# Rib.net
KiCad netlist of a schematic drawn in EAGLE
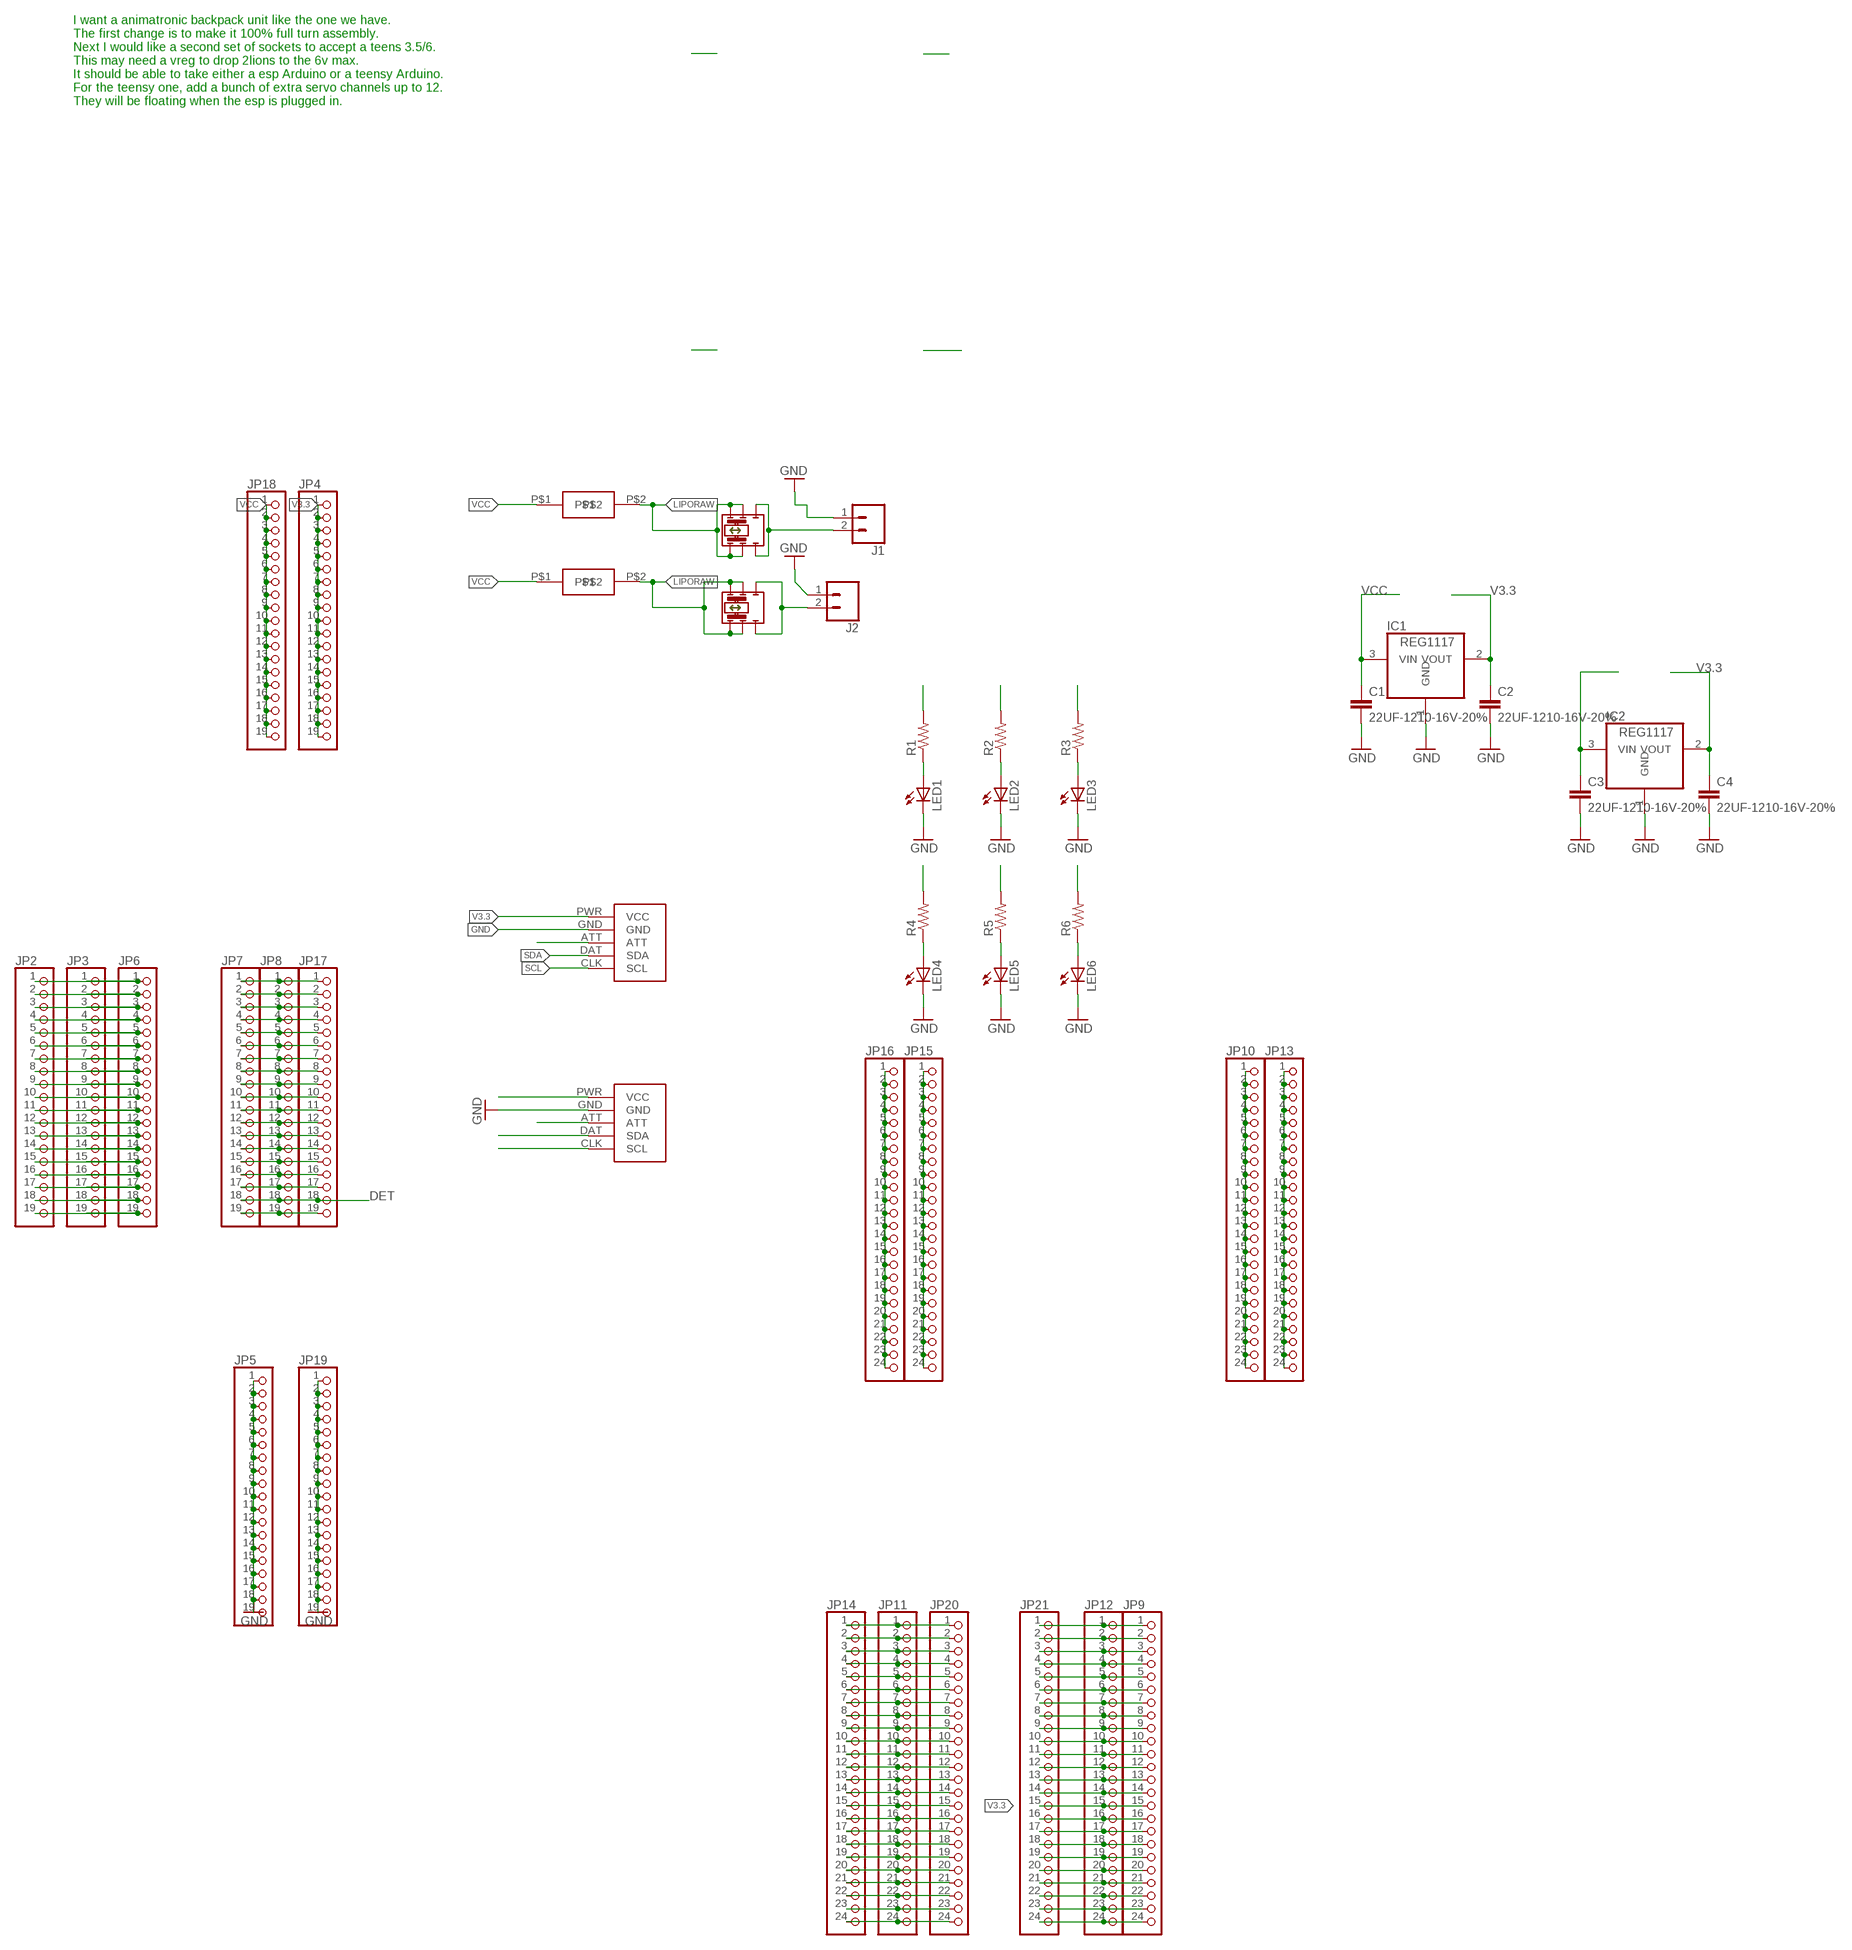
[diagram p0: schematic, sheet 1]

(export (version "E")
  (design (tool "Eeschema 10.0.6"))
  (components
    (comp (ref "C1")
      (value "22UF-1210-16V-20%")
      (footprint "eagle-import:1210")
      (libsource (lib "eagle-import") (part "22UF-1210-16V-20%"))
    )
    (comp (ref "C2")
      (value "22UF-1210-16V-20%")
      (footprint "eagle-import:1210")
      (libsource (lib "eagle-import") (part "22UF-1210-16V-20%"))
    )
    (comp (ref "C3")
      (value "22UF-1210-16V-20%")
      (footprint "eagle-import:1210")
      (libsource (lib "eagle-import") (part "22UF-1210-16V-20%"))
    )
    (comp (ref "C4")
      (value "22UF-1210-16V-20%")
      (footprint "eagle-import:1210")
      (libsource (lib "eagle-import") (part "22UF-1210-16V-20%"))
    )
    (comp (ref "F3")
      (value "3557-2")
      (footprint "eagle-import:3557-2")
      (libsource (lib "eagle-import") (part "3557-2"))
    )
    (comp (ref "F4")
      (value "3557-2")
      (footprint "eagle-import:3557-2")
      (libsource (lib "eagle-import") (part "3557-2"))
    )
    (comp (ref "IC1")
      (value "REG1117")
      (footprint "eagle-import:SOT223")
      (libsource (lib "eagle-import") (part "REG1117"))
    )
    (comp (ref "IC2")
      (value "REG1117")
      (footprint "eagle-import:SOT223")
      (libsource (lib "eagle-import") (part "REG1117"))
    )
    (comp (ref "J1")
      (value "CONN_023.5MM_LOCK")
      (footprint "eagle-import:SCREWTERMINAL-3.5MM-2_LOCK")
      (libsource (lib "eagle-import") (part "CONN_023.5MM_LOCK"))
    )
    (comp (ref "J2")
      (value "CONN_023.5MM_LOCK")
      (footprint "eagle-import:SCREWTERMINAL-3.5MM-2_LOCK")
      (libsource (lib "eagle-import") (part "CONN_023.5MM_LOCK"))
    )
    (comp (ref "JP2")
      (value "PINHD-1X19")
      (footprint "eagle-import:1X19")
      (libsource (lib "eagle-import") (part "PINHD-1X19"))
    )
    (comp (ref "JP3")
      (value "PINHD-1X19")
      (footprint "eagle-import:1X19")
      (libsource (lib "eagle-import") (part "PINHD-1X19"))
    )
    (comp (ref "JP4")
      (value "PINHD-1X19")
      (footprint "eagle-import:1X19")
      (libsource (lib "eagle-import") (part "PINHD-1X19"))
    )
    (comp (ref "JP5")
      (value "PINHD-1X19")
      (footprint "eagle-import:1X19")
      (libsource (lib "eagle-import") (part "PINHD-1X19"))
    )
    (comp (ref "JP6")
      (value "PINHD-1X19")
      (footprint "eagle-import:1X19")
      (libsource (lib "eagle-import") (part "PINHD-1X19"))
    )
    (comp (ref "JP7")
      (value "PINHD-1X19")
      (footprint "eagle-import:1X19")
      (libsource (lib "eagle-import") (part "PINHD-1X19"))
    )
    (comp (ref "JP8")
      (value "PINHD-1X19")
      (footprint "eagle-import:1X19")
      (libsource (lib "eagle-import") (part "PINHD-1X19"))
    )
    (comp (ref "JP9")
      (value "PINHD-1X24")
      (footprint "eagle-import:1X24")
      (libsource (lib "eagle-import") (part "PINHD-1X24"))
    )
    (comp (ref "JP10")
      (value "PINHD-1X24")
      (footprint "eagle-import:1X24")
      (libsource (lib "eagle-import") (part "PINHD-1X24"))
    )
    (comp (ref "JP11")
      (value "PINHD-1X24")
      (footprint "eagle-import:1X24")
      (libsource (lib "eagle-import") (part "PINHD-1X24"))
    )
    (comp (ref "JP12")
      (value "PINHD-1X24")
      (footprint "eagle-import:1X24")
      (libsource (lib "eagle-import") (part "PINHD-1X24"))
    )
    (comp (ref "JP13")
      (value "PINHD-1X24")
      (footprint "eagle-import:1X24")
      (libsource (lib "eagle-import") (part "PINHD-1X24"))
    )
    (comp (ref "JP14")
      (value "PINHD-1X24")
      (footprint "eagle-import:1X24")
      (libsource (lib "eagle-import") (part "PINHD-1X24"))
    )
    (comp (ref "JP15")
      (value "PINHD-1X24")
      (footprint "eagle-import:1X24")
      (libsource (lib "eagle-import") (part "PINHD-1X24"))
    )
    (comp (ref "JP16")
      (value "PINHD-1X24")
      (footprint "eagle-import:1X24")
      (libsource (lib "eagle-import") (part "PINHD-1X24"))
    )
    (comp (ref "JP17")
      (value "PINHD-1X19")
      (footprint "eagle-import:1X19")
      (libsource (lib "eagle-import") (part "PINHD-1X19"))
    )
    (comp (ref "JP18")
      (value "PINHD-1X19")
      (footprint "eagle-import:1X19")
      (libsource (lib "eagle-import") (part "PINHD-1X19"))
    )
    (comp (ref "JP19")
      (value "PINHD-1X19")
      (footprint "eagle-import:1X19")
      (libsource (lib "eagle-import") (part "PINHD-1X19"))
    )
    (comp (ref "JP20")
      (value "PINHD-1X24")
      (footprint "eagle-import:1X24")
      (libsource (lib "eagle-import") (part "PINHD-1X24"))
    )
    (comp (ref "JP21")
      (value "PINHD-1X24")
      (footprint "eagle-import:1X24")
      (libsource (lib "eagle-import") (part "PINHD-1X24"))
    )
    (comp (ref "LED1")
      (value "LED_ESML0603")
      (footprint "eagle-import:LED_SML0603")
      (libsource (lib "eagle-import") (part "LED_ESML0603"))
    )
    (comp (ref "LED2")
      (value "LED_ESML0603")
      (footprint "eagle-import:LED_SML0603")
      (libsource (lib "eagle-import") (part "LED_ESML0603"))
    )
    (comp (ref "LED3")
      (value "LED_ESML0603")
      (footprint "eagle-import:LED_SML0603")
      (libsource (lib "eagle-import") (part "LED_ESML0603"))
    )
    (comp (ref "LED4")
      (value "LED_ESML0603")
      (footprint "eagle-import:LED_SML0603")
      (libsource (lib "eagle-import") (part "LED_ESML0603"))
    )
    (comp (ref "LED5")
      (value "LED_ESML0603")
      (footprint "eagle-import:LED_SML0603")
      (libsource (lib "eagle-import") (part "LED_ESML0603"))
    )
    (comp (ref "LED6")
      (value "LED_ESML0603")
      (footprint "eagle-import:LED_SML0603")
      (libsource (lib "eagle-import") (part "LED_ESML0603"))
    )
    (comp (ref "R1")
      (value "R-US_R0603")
      (footprint "eagle-import:R0603")
      (libsource (lib "eagle-import") (part "R-US_R0603"))
    )
    (comp (ref "R2")
      (value "R-US_R0603")
      (footprint "eagle-import:R0603")
      (libsource (lib "eagle-import") (part "R-US_R0603"))
    )
    (comp (ref "R3")
      (value "R-US_R0603")
      (footprint "eagle-import:R0603")
      (libsource (lib "eagle-import") (part "R-US_R0603"))
    )
    (comp (ref "R4")
      (value "R-US_R0603")
      (footprint "eagle-import:R0603")
      (libsource (lib "eagle-import") (part "R-US_R0603"))
    )
    (comp (ref "R5")
      (value "R-US_R0603")
      (footprint "eagle-import:R0603")
      (libsource (lib "eagle-import") (part "R-US_R0603"))
    )
    (comp (ref "R6")
      (value "R-US_R0603")
      (footprint "eagle-import:R0603")
      (libsource (lib "eagle-import") (part "R-US_R0603"))
    )
    (comp (ref "SW1")
      (value "DPDT")
      (footprint "eagle-import:GF-126-0327")
      (libsource (lib "eagle-import") (part "DPDT"))
    )
    (comp (ref "SW2")
      (value "DPDT")
      (footprint "eagle-import:GF-126-0327")
      (libsource (lib "eagle-import") (part "DPDT"))
    )
    (comp (ref "U$3")
      (value "WIICHUCK")
      (footprint "eagle-import:CHUCK")
      (libsource (lib "eagle-import") (part "WIICHUCK"))
    )
    (comp (ref "U$5")
      (value "WIICHUCK")
      (footprint "eagle-import:CHUCK")
      (libsource (lib "eagle-import") (part "WIICHUCK"))
    )
  )
  (nets
    (net (code "1") (name "/5V") (class "Default")
      (node (ref "JP11") (pin "1") (pinfunction "1_1") (pintype "passive"))
      (node (ref "JP14") (pin "1") (pinfunction "1_1") (pintype "passive"))
      (node (ref "JP2") (pin "1") (pinfunction "1_1") (pintype "passive"))
      (node (ref "JP20") (pin "1") (pinfunction "1_1") (pintype "passive"))
      (node (ref "JP3") (pin "1") (pinfunction "1_1") (pintype "passive"))
      (node (ref "JP6") (pin "1") (pinfunction "1_1") (pintype "passive"))
    )
    (net (code "2") (name "/DET") (class "Default")
      (node (ref "JP12") (pin "24") (pinfunction "24_24") (pintype "passive"))
      (node (ref "JP17") (pin "18") (pinfunction "18_18") (pintype "passive"))
      (node (ref "JP21") (pin "24") (pinfunction "24_24") (pintype "passive"))
      (node (ref "JP7") (pin "18") (pinfunction "18_18") (pintype "passive"))
      (node (ref "JP8") (pin "18") (pinfunction "18_18") (pintype "passive"))
      (node (ref "JP9") (pin "24") (pinfunction "24_24") (pintype "passive"))
      (node (ref "U$3") (pin "ATT") (pinfunction "ATT_ATT") (pintype "bidirectional"))
      (node (ref "U$5") (pin "ATT") (pinfunction "ATT_ATT") (pintype "bidirectional"))
    )
    (net (code "3") (name "/RX0") (class "Default")
      (node (ref "JP12") (pin "12") (pinfunction "12_12") (pintype "passive"))
      (node (ref "JP17") (pin "15") (pinfunction "15_15") (pintype "passive"))
      (node (ref "JP21") (pin "12") (pinfunction "12_12") (pintype "passive"))
      (node (ref "JP7") (pin "15") (pinfunction "15_15") (pintype "passive"))
      (node (ref "JP8") (pin "15") (pinfunction "15_15") (pintype "passive"))
      (node (ref "JP9") (pin "12") (pinfunction "12_12") (pintype "passive"))
    )
    (net (code "4") (name "/TX0") (class "Default")
      (node (ref "JP12") (pin "11") (pinfunction "11_11") (pintype "passive"))
      (node (ref "JP17") (pin "16") (pinfunction "16_16") (pintype "passive"))
      (node (ref "JP21") (pin "11") (pinfunction "11_11") (pintype "passive"))
      (node (ref "JP7") (pin "16") (pinfunction "16_16") (pintype "passive"))
      (node (ref "JP8") (pin "16") (pinfunction "16_16") (pintype "passive"))
      (node (ref "JP9") (pin "11") (pinfunction "11_11") (pintype "passive"))
    )
    (net (code "5") (name "GND") (class "Default")
      (node (ref "C1") (pin "2") (pinfunction "2_2") (pintype "passive"))
      (node (ref "C2") (pin "2") (pinfunction "2_2") (pintype "passive"))
      (node (ref "C3") (pin "2") (pinfunction "2_2") (pintype "passive"))
      (node (ref "C4") (pin "2") (pinfunction "2_2") (pintype "passive"))
      (node (ref "IC1") (pin "1") (pinfunction "GND_1") (pintype "power_in"))
      (node (ref "IC2") (pin "1") (pinfunction "GND_1") (pintype "power_in"))
      (node (ref "J1") (pin "1") (pinfunction "1_1") (pintype "passive"))
      (node (ref "J2") (pin "1") (pinfunction "1_1") (pintype "passive"))
      (node (ref "JP11") (pin "15") (pinfunction "15_15") (pintype "passive"))
      (node (ref "JP11") (pin "2") (pinfunction "2_2") (pintype "passive"))
      (node (ref "JP12") (pin "1") (pinfunction "1_1") (pintype "passive"))
      (node (ref "JP13") (pin "1") (pinfunction "1_1") (pintype "passive"))
      (node (ref "JP13") (pin "10") (pinfunction "10_10") (pintype "passive"))
      (node (ref "JP13") (pin "11") (pinfunction "11_11") (pintype "passive"))
      (node (ref "JP13") (pin "12") (pinfunction "12_12") (pintype "passive"))
      (node (ref "JP13") (pin "13") (pinfunction "13_13") (pintype "passive"))
      (node (ref "JP13") (pin "14") (pinfunction "14_14") (pintype "passive"))
      (node (ref "JP13") (pin "15") (pinfunction "15_15") (pintype "passive"))
      (node (ref "JP13") (pin "16") (pinfunction "16_16") (pintype "passive"))
      (node (ref "JP13") (pin "17") (pinfunction "17_17") (pintype "passive"))
      (node (ref "JP13") (pin "18") (pinfunction "18_18") (pintype "passive"))
      (node (ref "JP13") (pin "19") (pinfunction "19_19") (pintype "passive"))
      (node (ref "JP13") (pin "2") (pinfunction "2_2") (pintype "passive"))
      (node (ref "JP13") (pin "20") (pinfunction "20_20") (pintype "passive"))
      (node (ref "JP13") (pin "21") (pinfunction "21_21") (pintype "passive"))
      (node (ref "JP13") (pin "22") (pinfunction "22_22") (pintype "passive"))
      (node (ref "JP13") (pin "23") (pinfunction "23_23") (pintype "passive"))
      (node (ref "JP13") (pin "24") (pinfunction "24_24") (pintype "passive"))
      (node (ref "JP13") (pin "3") (pinfunction "3_3") (pintype "passive"))
      (node (ref "JP13") (pin "4") (pinfunction "4_4") (pintype "passive"))
      (node (ref "JP13") (pin "5") (pinfunction "5_5") (pintype "passive"))
      (node (ref "JP13") (pin "6") (pinfunction "6_6") (pintype "passive"))
      (node (ref "JP13") (pin "7") (pinfunction "7_7") (pintype "passive"))
      (node (ref "JP13") (pin "8") (pinfunction "8_8") (pintype "passive"))
      (node (ref "JP13") (pin "9") (pinfunction "9_9") (pintype "passive"))
      (node (ref "JP14") (pin "15") (pinfunction "15_15") (pintype "passive"))
      (node (ref "JP14") (pin "2") (pinfunction "2_2") (pintype "passive"))
      (node (ref "JP16") (pin "1") (pinfunction "1_1") (pintype "passive"))
      (node (ref "JP16") (pin "10") (pinfunction "10_10") (pintype "passive"))
      (node (ref "JP16") (pin "11") (pinfunction "11_11") (pintype "passive"))
      (node (ref "JP16") (pin "12") (pinfunction "12_12") (pintype "passive"))
      (node (ref "JP16") (pin "13") (pinfunction "13_13") (pintype "passive"))
      (node (ref "JP16") (pin "14") (pinfunction "14_14") (pintype "passive"))
      (node (ref "JP16") (pin "15") (pinfunction "15_15") (pintype "passive"))
      (node (ref "JP16") (pin "16") (pinfunction "16_16") (pintype "passive"))
      (node (ref "JP16") (pin "17") (pinfunction "17_17") (pintype "passive"))
      (node (ref "JP16") (pin "18") (pinfunction "18_18") (pintype "passive"))
      (node (ref "JP16") (pin "19") (pinfunction "19_19") (pintype "passive"))
      (node (ref "JP16") (pin "2") (pinfunction "2_2") (pintype "passive"))
      (node (ref "JP16") (pin "20") (pinfunction "20_20") (pintype "passive"))
      (node (ref "JP16") (pin "21") (pinfunction "21_21") (pintype "passive"))
      (node (ref "JP16") (pin "22") (pinfunction "22_22") (pintype "passive"))
      (node (ref "JP16") (pin "23") (pinfunction "23_23") (pintype "passive"))
      (node (ref "JP16") (pin "24") (pinfunction "24_24") (pintype "passive"))
      (node (ref "JP16") (pin "3") (pinfunction "3_3") (pintype "passive"))
      (node (ref "JP16") (pin "4") (pinfunction "4_4") (pintype "passive"))
      (node (ref "JP16") (pin "5") (pinfunction "5_5") (pintype "passive"))
      (node (ref "JP16") (pin "6") (pinfunction "6_6") (pintype "passive"))
      (node (ref "JP16") (pin "7") (pinfunction "7_7") (pintype "passive"))
      (node (ref "JP16") (pin "8") (pinfunction "8_8") (pintype "passive"))
      (node (ref "JP16") (pin "9") (pinfunction "9_9") (pintype "passive"))
      (node (ref "JP17") (pin "13") (pinfunction "13_13") (pintype "passive"))
      (node (ref "JP17") (pin "19") (pinfunction "19_19") (pintype "passive"))
      (node (ref "JP19") (pin "1") (pinfunction "1_1") (pintype "passive"))
      (node (ref "JP19") (pin "10") (pinfunction "10_10") (pintype "passive"))
      (node (ref "JP19") (pin "11") (pinfunction "11_11") (pintype "passive"))
      (node (ref "JP19") (pin "12") (pinfunction "12_12") (pintype "passive"))
      (node (ref "JP19") (pin "13") (pinfunction "13_13") (pintype "passive"))
      (node (ref "JP19") (pin "14") (pinfunction "14_14") (pintype "passive"))
      (node (ref "JP19") (pin "15") (pinfunction "15_15") (pintype "passive"))
      (node (ref "JP19") (pin "16") (pinfunction "16_16") (pintype "passive"))
      (node (ref "JP19") (pin "17") (pinfunction "17_17") (pintype "passive"))
      (node (ref "JP19") (pin "18") (pinfunction "18_18") (pintype "passive"))
      (node (ref "JP19") (pin "19") (pinfunction "19_19") (pintype "passive"))
      (node (ref "JP19") (pin "2") (pinfunction "2_2") (pintype "passive"))
      (node (ref "JP19") (pin "3") (pinfunction "3_3") (pintype "passive"))
      (node (ref "JP19") (pin "4") (pinfunction "4_4") (pintype "passive"))
      (node (ref "JP19") (pin "5") (pinfunction "5_5") (pintype "passive"))
      (node (ref "JP19") (pin "6") (pinfunction "6_6") (pintype "passive"))
      (node (ref "JP19") (pin "7") (pinfunction "7_7") (pintype "passive"))
      (node (ref "JP19") (pin "8") (pinfunction "8_8") (pintype "passive"))
      (node (ref "JP19") (pin "9") (pinfunction "9_9") (pintype "passive"))
      (node (ref "JP2") (pin "6") (pinfunction "6_6") (pintype "passive"))
      (node (ref "JP20") (pin "15") (pinfunction "15_15") (pintype "passive"))
      (node (ref "JP20") (pin "2") (pinfunction "2_2") (pintype "passive"))
      (node (ref "JP21") (pin "1") (pinfunction "1_1") (pintype "passive"))
      (node (ref "JP3") (pin "6") (pinfunction "6_6") (pintype "passive"))
      (node (ref "JP5") (pin "1") (pinfunction "1_1") (pintype "passive"))
      (node (ref "JP5") (pin "10") (pinfunction "10_10") (pintype "passive"))
      (node (ref "JP5") (pin "11") (pinfunction "11_11") (pintype "passive"))
      (node (ref "JP5") (pin "12") (pinfunction "12_12") (pintype "passive"))
      (node (ref "JP5") (pin "13") (pinfunction "13_13") (pintype "passive"))
      (node (ref "JP5") (pin "14") (pinfunction "14_14") (pintype "passive"))
      (node (ref "JP5") (pin "15") (pinfunction "15_15") (pintype "passive"))
      (node (ref "JP5") (pin "16") (pinfunction "16_16") (pintype "passive"))
      (node (ref "JP5") (pin "17") (pinfunction "17_17") (pintype "passive"))
      (node (ref "JP5") (pin "18") (pinfunction "18_18") (pintype "passive"))
      (node (ref "JP5") (pin "19") (pinfunction "19_19") (pintype "passive"))
      (node (ref "JP5") (pin "2") (pinfunction "2_2") (pintype "passive"))
      (node (ref "JP5") (pin "3") (pinfunction "3_3") (pintype "passive"))
      (node (ref "JP5") (pin "4") (pinfunction "4_4") (pintype "passive"))
      (node (ref "JP5") (pin "5") (pinfunction "5_5") (pintype "passive"))
      (node (ref "JP5") (pin "6") (pinfunction "6_6") (pintype "passive"))
      (node (ref "JP5") (pin "7") (pinfunction "7_7") (pintype "passive"))
      (node (ref "JP5") (pin "8") (pinfunction "8_8") (pintype "passive"))
      (node (ref "JP5") (pin "9") (pinfunction "9_9") (pintype "passive"))
      (node (ref "JP6") (pin "6") (pinfunction "6_6") (pintype "passive"))
      (node (ref "JP7") (pin "13") (pinfunction "13_13") (pintype "passive"))
      (node (ref "JP7") (pin "19") (pinfunction "19_19") (pintype "passive"))
      (node (ref "JP8") (pin "13") (pinfunction "13_13") (pintype "passive"))
      (node (ref "JP8") (pin "19") (pinfunction "19_19") (pintype "passive"))
      (node (ref "JP9") (pin "1") (pinfunction "1_1") (pintype "passive"))
      (node (ref "LED1") (pin "C") (pinfunction "C_C") (pintype "passive"))
      (node (ref "LED2") (pin "C") (pinfunction "C_C") (pintype "passive"))
      (node (ref "LED3") (pin "C") (pinfunction "C_C") (pintype "passive"))
      (node (ref "LED4") (pin "C") (pinfunction "C_C") (pintype "passive"))
      (node (ref "LED5") (pin "C") (pinfunction "C_C") (pintype "passive"))
      (node (ref "LED6") (pin "C") (pinfunction "C_C") (pintype "passive"))
      (node (ref "U$3") (pin "GND") (pinfunction "GND_GND") (pintype "bidirectional"))
      (node (ref "U$5") (pin "GND") (pinfunction "GND_GND") (pintype "bidirectional"))
    )
    (net (code "6") (name "LIPORAW") (class "Default")
      (node (ref "F3") (pin "P$2") (pinfunction "P$2_P$2") (pintype "bidirectional"))
      (node (ref "F4") (pin "P$2") (pinfunction "P$2_P$2") (pintype "bidirectional"))
      (node (ref "R2") (pin "2") (pinfunction "2_2") (pintype "passive"))
      (node (ref "R5") (pin "2") (pinfunction "2_2") (pintype "passive"))
      (node (ref "SW1") (pin "A1") (pinfunction "A1_A1") (pintype "bidirectional"))
      (node (ref "SW1") (pin "A2") (pinfunction "A2_A2") (pintype "bidirectional"))
      (node (ref "SW1") (pin "B1") (pinfunction "B1_B1") (pintype "bidirectional"))
      (node (ref "SW1") (pin "B2") (pinfunction "B2_B2") (pintype "bidirectional"))
      (node (ref "SW2") (pin "A1") (pinfunction "A1_A1") (pintype "bidirectional"))
      (node (ref "SW2") (pin "A2") (pinfunction "A2_A2") (pintype "bidirectional"))
      (node (ref "SW2") (pin "B1") (pinfunction "B1_B1") (pintype "bidirectional"))
      (node (ref "SW2") (pin "B2") (pinfunction "B2_B2") (pintype "bidirectional"))
    )
    (net (code "7") (name "Net-(J1-Pad2)") (class "Default")
      (node (ref "J1") (pin "2") (pinfunction "2_2") (pintype "passive"))
      (node (ref "SW1") (pin "C1") (pinfunction "C1_C1") (pintype "bidirectional"))
      (node (ref "SW1") (pin "C2") (pinfunction "C2_C2") (pintype "bidirectional"))
    )
    (net (code "8") (name "Net-(J2-Pad2)") (class "Default")
      (node (ref "J2") (pin "2") (pinfunction "2_2") (pintype "passive"))
      (node (ref "SW2") (pin "C1") (pinfunction "C1_C1") (pintype "bidirectional"))
      (node (ref "SW2") (pin "C2") (pinfunction "C2_C2") (pintype "bidirectional"))
    )
    (net (code "9") (name "Net-(JP2-Pad2)") (class "Default")
      (node (ref "JP2") (pin "2") (pinfunction "2_2") (pintype "passive"))
      (node (ref "JP3") (pin "2") (pinfunction "2_2") (pintype "passive"))
      (node (ref "JP6") (pin "2") (pinfunction "2_2") (pintype "passive"))
    )
    (net (code "10") (name "Net-(JP2-Pad3)") (class "Default")
      (node (ref "JP2") (pin "3") (pinfunction "3_3") (pintype "passive"))
      (node (ref "JP3") (pin "3") (pinfunction "3_3") (pintype "passive"))
      (node (ref "JP6") (pin "3") (pinfunction "3_3") (pintype "passive"))
    )
    (net (code "11") (name "Net-(JP2-Pad4)") (class "Default")
      (node (ref "JP2") (pin "4") (pinfunction "4_4") (pintype "passive"))
      (node (ref "JP3") (pin "4") (pinfunction "4_4") (pintype "passive"))
      (node (ref "JP6") (pin "4") (pinfunction "4_4") (pintype "passive"))
    )
    (net (code "12") (name "Net-(JP2-Pad5)") (class "Default")
      (node (ref "JP2") (pin "5") (pinfunction "5_5") (pintype "passive"))
      (node (ref "JP3") (pin "5") (pinfunction "5_5") (pintype "passive"))
      (node (ref "JP6") (pin "5") (pinfunction "5_5") (pintype "passive"))
    )
    (net (code "13") (name "Net-(JP2-Pad7)") (class "Default")
      (node (ref "JP2") (pin "7") (pinfunction "7_7") (pintype "passive"))
      (node (ref "JP3") (pin "7") (pinfunction "7_7") (pintype "passive"))
      (node (ref "JP6") (pin "7") (pinfunction "7_7") (pintype "passive"))
    )
    (net (code "14") (name "Net-(JP2-Pad8)") (class "Default")
      (node (ref "JP2") (pin "8") (pinfunction "8_8") (pintype "passive"))
      (node (ref "JP3") (pin "8") (pinfunction "8_8") (pintype "passive"))
      (node (ref "JP6") (pin "8") (pinfunction "8_8") (pintype "passive"))
    )
    (net (code "15") (name "Net-(JP2-Pad9)") (class "Default")
      (node (ref "JP2") (pin "9") (pinfunction "9_9") (pintype "passive"))
      (node (ref "JP3") (pin "9") (pinfunction "9_9") (pintype "passive"))
      (node (ref "JP6") (pin "9") (pinfunction "9_9") (pintype "passive"))
    )
    (net (code "16") (name "Net-(JP2-Pad10)") (class "Default")
      (node (ref "JP2") (pin "10") (pinfunction "10_10") (pintype "passive"))
      (node (ref "JP3") (pin "10") (pinfunction "10_10") (pintype "passive"))
      (node (ref "JP6") (pin "10") (pinfunction "10_10") (pintype "passive"))
    )
    (net (code "17") (name "Net-(JP2-Pad11)") (class "Default")
      (node (ref "JP2") (pin "11") (pinfunction "11_11") (pintype "passive"))
      (node (ref "JP3") (pin "11") (pinfunction "11_11") (pintype "passive"))
      (node (ref "JP6") (pin "11") (pinfunction "11_11") (pintype "passive"))
    )
    (net (code "18") (name "Net-(JP2-Pad12)") (class "Default")
      (node (ref "JP2") (pin "12") (pinfunction "12_12") (pintype "passive"))
      (node (ref "JP3") (pin "12") (pinfunction "12_12") (pintype "passive"))
      (node (ref "JP6") (pin "12") (pinfunction "12_12") (pintype "passive"))
    )
    (net (code "19") (name "Net-(JP2-Pad13)") (class "Default")
      (node (ref "JP2") (pin "13") (pinfunction "13_13") (pintype "passive"))
      (node (ref "JP3") (pin "13") (pinfunction "13_13") (pintype "passive"))
      (node (ref "JP6") (pin "13") (pinfunction "13_13") (pintype "passive"))
    )
    (net (code "20") (name "Net-(JP2-Pad14)") (class "Default")
      (node (ref "JP2") (pin "14") (pinfunction "14_14") (pintype "passive"))
      (node (ref "JP3") (pin "14") (pinfunction "14_14") (pintype "passive"))
      (node (ref "JP6") (pin "14") (pinfunction "14_14") (pintype "passive"))
    )
    (net (code "21") (name "Net-(JP2-Pad15)") (class "Default")
      (node (ref "JP2") (pin "15") (pinfunction "15_15") (pintype "passive"))
      (node (ref "JP3") (pin "15") (pinfunction "15_15") (pintype "passive"))
      (node (ref "JP6") (pin "15") (pinfunction "15_15") (pintype "passive"))
    )
    (net (code "22") (name "Net-(JP2-Pad16)") (class "Default")
      (node (ref "JP2") (pin "16") (pinfunction "16_16") (pintype "passive"))
      (node (ref "JP3") (pin "16") (pinfunction "16_16") (pintype "passive"))
      (node (ref "JP6") (pin "16") (pinfunction "16_16") (pintype "passive"))
    )
    (net (code "23") (name "Net-(JP2-Pad17)") (class "Default")
      (node (ref "JP2") (pin "17") (pinfunction "17_17") (pintype "passive"))
      (node (ref "JP3") (pin "17") (pinfunction "17_17") (pintype "passive"))
      (node (ref "JP6") (pin "17") (pinfunction "17_17") (pintype "passive"))
    )
    (net (code "24") (name "Net-(JP2-Pad18)") (class "Default")
      (node (ref "JP2") (pin "18") (pinfunction "18_18") (pintype "passive"))
      (node (ref "JP3") (pin "18") (pinfunction "18_18") (pintype "passive"))
      (node (ref "JP6") (pin "18") (pinfunction "18_18") (pintype "passive"))
    )
    (net (code "25") (name "Net-(JP11-Pad3)") (class "Default")
      (node (ref "JP11") (pin "3") (pinfunction "3_3") (pintype "passive"))
      (node (ref "JP14") (pin "3") (pinfunction "3_3") (pintype "passive"))
      (node (ref "JP20") (pin "3") (pinfunction "3_3") (pintype "passive"))
    )
    (net (code "26") (name "Net-(JP11-Pad4)") (class "Default")
      (node (ref "JP11") (pin "4") (pinfunction "4_4") (pintype "passive"))
      (node (ref "JP14") (pin "4") (pinfunction "4_4") (pintype "passive"))
      (node (ref "JP20") (pin "4") (pinfunction "4_4") (pintype "passive"))
    )
    (net (code "27") (name "Net-(JP11-Pad5)") (class "Default")
      (node (ref "JP11") (pin "5") (pinfunction "5_5") (pintype "passive"))
      (node (ref "JP14") (pin "5") (pinfunction "5_5") (pintype "passive"))
      (node (ref "JP20") (pin "5") (pinfunction "5_5") (pintype "passive"))
    )
    (net (code "28") (name "Net-(JP11-Pad6)") (class "Default")
      (node (ref "JP11") (pin "6") (pinfunction "6_6") (pintype "passive"))
      (node (ref "JP14") (pin "6") (pinfunction "6_6") (pintype "passive"))
      (node (ref "JP20") (pin "6") (pinfunction "6_6") (pintype "passive"))
    )
    (net (code "29") (name "Net-(JP11-Pad7)") (class "Default")
      (node (ref "JP11") (pin "7") (pinfunction "7_7") (pintype "passive"))
      (node (ref "JP14") (pin "7") (pinfunction "7_7") (pintype "passive"))
      (node (ref "JP20") (pin "7") (pinfunction "7_7") (pintype "passive"))
    )
    (net (code "30") (name "Net-(JP11-Pad10)") (class "Default")
      (node (ref "JP11") (pin "10") (pinfunction "10_10") (pintype "passive"))
      (node (ref "JP14") (pin "10") (pinfunction "10_10") (pintype "passive"))
      (node (ref "JP20") (pin "10") (pinfunction "10_10") (pintype "passive"))
    )
    (net (code "31") (name "Net-(JP11-Pad11)") (class "Default")
      (node (ref "JP11") (pin "11") (pinfunction "11_11") (pintype "passive"))
      (node (ref "JP14") (pin "11") (pinfunction "11_11") (pintype "passive"))
      (node (ref "JP20") (pin "11") (pinfunction "11_11") (pintype "passive"))
    )
    (net (code "32") (name "Net-(JP11-Pad12)") (class "Default")
      (node (ref "JP11") (pin "12") (pinfunction "12_12") (pintype "passive"))
      (node (ref "JP14") (pin "12") (pinfunction "12_12") (pintype "passive"))
      (node (ref "JP20") (pin "12") (pinfunction "12_12") (pintype "passive"))
    )
    (net (code "33") (name "Net-(JP11-Pad13)") (class "Default")
      (node (ref "JP11") (pin "13") (pinfunction "13_13") (pintype "passive"))
      (node (ref "JP14") (pin "13") (pinfunction "13_13") (pintype "passive"))
      (node (ref "JP20") (pin "13") (pinfunction "13_13") (pintype "passive"))
    )
    (net (code "34") (name "Net-(JP11-Pad14)") (class "Default")
      (node (ref "JP11") (pin "14") (pinfunction "14_14") (pintype "passive"))
      (node (ref "JP14") (pin "14") (pinfunction "14_14") (pintype "passive"))
      (node (ref "JP20") (pin "14") (pinfunction "14_14") (pintype "passive"))
    )
    (net (code "35") (name "Net-(JP11-Pad16)") (class "Default")
      (node (ref "JP11") (pin "16") (pinfunction "16_16") (pintype "passive"))
      (node (ref "JP14") (pin "16") (pinfunction "16_16") (pintype "passive"))
      (node (ref "JP20") (pin "16") (pinfunction "16_16") (pintype "passive"))
    )
    (net (code "36") (name "Net-(JP11-Pad17)") (class "Default")
      (node (ref "JP11") (pin "17") (pinfunction "17_17") (pintype "passive"))
      (node (ref "JP14") (pin "17") (pinfunction "17_17") (pintype "passive"))
      (node (ref "JP20") (pin "17") (pinfunction "17_17") (pintype "passive"))
    )
    (net (code "37") (name "Net-(JP11-Pad18)") (class "Default")
      (node (ref "JP11") (pin "18") (pinfunction "18_18") (pintype "passive"))
      (node (ref "JP14") (pin "18") (pinfunction "18_18") (pintype "passive"))
      (node (ref "JP20") (pin "18") (pinfunction "18_18") (pintype "passive"))
    )
    (net (code "38") (name "Net-(JP11-Pad19)") (class "Default")
      (node (ref "JP11") (pin "19") (pinfunction "19_19") (pintype "passive"))
      (node (ref "JP14") (pin "19") (pinfunction "19_19") (pintype "passive"))
      (node (ref "JP20") (pin "19") (pinfunction "19_19") (pintype "passive"))
    )
    (net (code "39") (name "Net-(JP11-Pad20)") (class "Default")
      (node (ref "JP11") (pin "20") (pinfunction "20_20") (pintype "passive"))
      (node (ref "JP14") (pin "20") (pinfunction "20_20") (pintype "passive"))
      (node (ref "JP20") (pin "20") (pinfunction "20_20") (pintype "passive"))
    )
    (net (code "40") (name "Net-(JP11-Pad21)") (class "Default")
      (node (ref "JP11") (pin "21") (pinfunction "21_21") (pintype "passive"))
      (node (ref "JP14") (pin "21") (pinfunction "21_21") (pintype "passive"))
      (node (ref "JP20") (pin "21") (pinfunction "21_21") (pintype "passive"))
    )
    (net (code "41") (name "Net-(JP11-Pad22)") (class "Default")
      (node (ref "JP11") (pin "22") (pinfunction "22_22") (pintype "passive"))
      (node (ref "JP14") (pin "22") (pinfunction "22_22") (pintype "passive"))
      (node (ref "JP20") (pin "22") (pinfunction "22_22") (pintype "passive"))
    )
    (net (code "42") (name "Net-(JP11-Pad23)") (class "Default")
      (node (ref "JP11") (pin "23") (pinfunction "23_23") (pintype "passive"))
      (node (ref "JP14") (pin "23") (pinfunction "23_23") (pintype "passive"))
      (node (ref "JP20") (pin "23") (pinfunction "23_23") (pintype "passive"))
    )
    (net (code "43") (name "Net-(JP11-Pad24)") (class "Default")
      (node (ref "JP11") (pin "24") (pinfunction "24_24") (pintype "passive"))
      (node (ref "JP14") (pin "24") (pinfunction "24_24") (pintype "passive"))
      (node (ref "JP20") (pin "24") (pinfunction "24_24") (pintype "passive"))
    )
    (net (code "44") (name "Net-(JP12-Pad2)") (class "Default")
      (node (ref "JP12") (pin "2") (pinfunction "2_2") (pintype "passive"))
      (node (ref "JP21") (pin "2") (pinfunction "2_2") (pintype "passive"))
      (node (ref "JP9") (pin "2") (pinfunction "2_2") (pintype "passive"))
    )
    (net (code "45") (name "Net-(JP12-Pad3)") (class "Default")
      (node (ref "JP12") (pin "3") (pinfunction "3_3") (pintype "passive"))
      (node (ref "JP21") (pin "3") (pinfunction "3_3") (pintype "passive"))
      (node (ref "JP9") (pin "3") (pinfunction "3_3") (pintype "passive"))
    )
    (net (code "46") (name "Net-(JP12-Pad4)") (class "Default")
      (node (ref "JP12") (pin "4") (pinfunction "4_4") (pintype "passive"))
      (node (ref "JP21") (pin "4") (pinfunction "4_4") (pintype "passive"))
      (node (ref "JP9") (pin "4") (pinfunction "4_4") (pintype "passive"))
    )
    (net (code "47") (name "Net-(JP12-Pad5)") (class "Default")
      (node (ref "JP12") (pin "5") (pinfunction "5_5") (pintype "passive"))
      (node (ref "JP21") (pin "5") (pinfunction "5_5") (pintype "passive"))
      (node (ref "JP9") (pin "5") (pinfunction "5_5") (pintype "passive"))
    )
    (net (code "48") (name "Net-(JP12-Pad6)") (class "Default")
      (node (ref "JP12") (pin "6") (pinfunction "6_6") (pintype "passive"))
      (node (ref "JP21") (pin "6") (pinfunction "6_6") (pintype "passive"))
      (node (ref "JP9") (pin "6") (pinfunction "6_6") (pintype "passive"))
    )
    (net (code "49") (name "Net-(JP12-Pad7)") (class "Default")
      (node (ref "JP12") (pin "7") (pinfunction "7_7") (pintype "passive"))
      (node (ref "JP21") (pin "7") (pinfunction "7_7") (pintype "passive"))
      (node (ref "JP9") (pin "7") (pinfunction "7_7") (pintype "passive"))
    )
    (net (code "50") (name "Net-(JP12-Pad8)") (class "Default")
      (node (ref "JP12") (pin "8") (pinfunction "8_8") (pintype "passive"))
      (node (ref "JP21") (pin "8") (pinfunction "8_8") (pintype "passive"))
      (node (ref "JP9") (pin "8") (pinfunction "8_8") (pintype "passive"))
    )
    (net (code "51") (name "Net-(JP12-Pad9)") (class "Default")
      (node (ref "JP12") (pin "9") (pinfunction "9_9") (pintype "passive"))
      (node (ref "JP21") (pin "9") (pinfunction "9_9") (pintype "passive"))
      (node (ref "JP9") (pin "9") (pinfunction "9_9") (pintype "passive"))
    )
    (net (code "52") (name "Net-(JP12-Pad10)") (class "Default")
      (node (ref "JP12") (pin "10") (pinfunction "10_10") (pintype "passive"))
      (node (ref "JP21") (pin "10") (pinfunction "10_10") (pintype "passive"))
      (node (ref "JP9") (pin "10") (pinfunction "10_10") (pintype "passive"))
    )
    (net (code "53") (name "Net-(JP12-Pad13)") (class "Default")
      (node (ref "JP12") (pin "13") (pinfunction "13_13") (pintype "passive"))
      (node (ref "JP21") (pin "13") (pinfunction "13_13") (pintype "passive"))
      (node (ref "JP9") (pin "13") (pinfunction "13_13") (pintype "passive"))
    )
    (net (code "54") (name "Net-(JP12-Pad14)") (class "Default")
      (node (ref "JP12") (pin "14") (pinfunction "14_14") (pintype "passive"))
      (node (ref "JP21") (pin "14") (pinfunction "14_14") (pintype "passive"))
      (node (ref "JP9") (pin "14") (pinfunction "14_14") (pintype "passive"))
    )
    (net (code "55") (name "Net-(JP12-Pad16)") (class "Default")
      (node (ref "JP12") (pin "16") (pinfunction "16_16") (pintype "passive"))
      (node (ref "JP21") (pin "16") (pinfunction "16_16") (pintype "passive"))
      (node (ref "JP9") (pin "16") (pinfunction "16_16") (pintype "passive"))
    )
    (net (code "56") (name "Net-(JP12-Pad17)") (class "Default")
      (node (ref "JP12") (pin "17") (pinfunction "17_17") (pintype "passive"))
      (node (ref "JP21") (pin "17") (pinfunction "17_17") (pintype "passive"))
      (node (ref "JP9") (pin "17") (pinfunction "17_17") (pintype "passive"))
    )
    (net (code "57") (name "Net-(JP12-Pad18)") (class "Default")
      (node (ref "JP12") (pin "18") (pinfunction "18_18") (pintype "passive"))
      (node (ref "JP21") (pin "18") (pinfunction "18_18") (pintype "passive"))
      (node (ref "JP9") (pin "18") (pinfunction "18_18") (pintype "passive"))
    )
    (net (code "58") (name "Net-(JP12-Pad19)") (class "Default")
      (node (ref "JP12") (pin "19") (pinfunction "19_19") (pintype "passive"))
      (node (ref "JP21") (pin "19") (pinfunction "19_19") (pintype "passive"))
      (node (ref "JP9") (pin "19") (pinfunction "19_19") (pintype "passive"))
    )
    (net (code "59") (name "Net-(JP12-Pad20)") (class "Default")
      (node (ref "JP12") (pin "20") (pinfunction "20_20") (pintype "passive"))
      (node (ref "JP21") (pin "20") (pinfunction "20_20") (pintype "passive"))
      (node (ref "JP9") (pin "20") (pinfunction "20_20") (pintype "passive"))
    )
    (net (code "60") (name "Net-(JP12-Pad21)") (class "Default")
      (node (ref "JP12") (pin "21") (pinfunction "21_21") (pintype "passive"))
      (node (ref "JP21") (pin "21") (pinfunction "21_21") (pintype "passive"))
      (node (ref "JP9") (pin "21") (pinfunction "21_21") (pintype "passive"))
    )
    (net (code "61") (name "Net-(JP12-Pad22)") (class "Default")
      (node (ref "JP12") (pin "22") (pinfunction "22_22") (pintype "passive"))
      (node (ref "JP21") (pin "22") (pinfunction "22_22") (pintype "passive"))
      (node (ref "JP9") (pin "22") (pinfunction "22_22") (pintype "passive"))
    )
    (net (code "62") (name "Net-(JP12-Pad23)") (class "Default")
      (node (ref "JP12") (pin "23") (pinfunction "23_23") (pintype "passive"))
      (node (ref "JP21") (pin "23") (pinfunction "23_23") (pintype "passive"))
      (node (ref "JP9") (pin "23") (pinfunction "23_23") (pintype "passive"))
    )
    (net (code "63") (name "Net-(JP17-Pad1)") (class "Default")
      (node (ref "JP17") (pin "1") (pinfunction "1_1") (pintype "passive"))
      (node (ref "JP7") (pin "1") (pinfunction "1_1") (pintype "passive"))
      (node (ref "JP8") (pin "1") (pinfunction "1_1") (pintype "passive"))
    )
    (net (code "64") (name "Net-(JP17-Pad2)") (class "Default")
      (node (ref "JP17") (pin "2") (pinfunction "2_2") (pintype "passive"))
      (node (ref "JP7") (pin "2") (pinfunction "2_2") (pintype "passive"))
      (node (ref "JP8") (pin "2") (pinfunction "2_2") (pintype "passive"))
    )
    (net (code "65") (name "Net-(JP17-Pad3)") (class "Default")
      (node (ref "JP17") (pin "3") (pinfunction "3_3") (pintype "passive"))
      (node (ref "JP7") (pin "3") (pinfunction "3_3") (pintype "passive"))
      (node (ref "JP8") (pin "3") (pinfunction "3_3") (pintype "passive"))
    )
    (net (code "66") (name "Net-(JP17-Pad4)") (class "Default")
      (node (ref "JP17") (pin "4") (pinfunction "4_4") (pintype "passive"))
      (node (ref "JP7") (pin "4") (pinfunction "4_4") (pintype "passive"))
      (node (ref "JP8") (pin "4") (pinfunction "4_4") (pintype "passive"))
    )
    (net (code "67") (name "Net-(JP17-Pad5)") (class "Default")
      (node (ref "JP17") (pin "5") (pinfunction "5_5") (pintype "passive"))
      (node (ref "JP7") (pin "5") (pinfunction "5_5") (pintype "passive"))
      (node (ref "JP8") (pin "5") (pinfunction "5_5") (pintype "passive"))
    )
    (net (code "68") (name "Net-(JP17-Pad6)") (class "Default")
      (node (ref "JP17") (pin "6") (pinfunction "6_6") (pintype "passive"))
      (node (ref "JP7") (pin "6") (pinfunction "6_6") (pintype "passive"))
      (node (ref "JP8") (pin "6") (pinfunction "6_6") (pintype "passive"))
    )
    (net (code "69") (name "Net-(JP17-Pad7)") (class "Default")
      (node (ref "JP17") (pin "7") (pinfunction "7_7") (pintype "passive"))
      (node (ref "JP7") (pin "7") (pinfunction "7_7") (pintype "passive"))
      (node (ref "JP8") (pin "7") (pinfunction "7_7") (pintype "passive"))
    )
    (net (code "70") (name "Net-(JP17-Pad8)") (class "Default")
      (node (ref "JP17") (pin "8") (pinfunction "8_8") (pintype "passive"))
      (node (ref "JP7") (pin "8") (pinfunction "8_8") (pintype "passive"))
      (node (ref "JP8") (pin "8") (pinfunction "8_8") (pintype "passive"))
    )
    (net (code "71") (name "Net-(JP17-Pad9)") (class "Default")
      (node (ref "JP17") (pin "9") (pinfunction "9_9") (pintype "passive"))
      (node (ref "JP7") (pin "9") (pinfunction "9_9") (pintype "passive"))
      (node (ref "JP8") (pin "9") (pinfunction "9_9") (pintype "passive"))
    )
    (net (code "72") (name "Net-(JP17-Pad10)") (class "Default")
      (node (ref "JP17") (pin "10") (pinfunction "10_10") (pintype "passive"))
      (node (ref "JP7") (pin "10") (pinfunction "10_10") (pintype "passive"))
      (node (ref "JP8") (pin "10") (pinfunction "10_10") (pintype "passive"))
    )
    (net (code "73") (name "Net-(JP17-Pad11)") (class "Default")
      (node (ref "JP17") (pin "11") (pinfunction "11_11") (pintype "passive"))
      (node (ref "JP7") (pin "11") (pinfunction "11_11") (pintype "passive"))
      (node (ref "JP8") (pin "11") (pinfunction "11_11") (pintype "passive"))
    )
    (net (code "74") (name "Net-(JP17-Pad12)") (class "Default")
      (node (ref "JP17") (pin "12") (pinfunction "12_12") (pintype "passive"))
      (node (ref "JP7") (pin "12") (pinfunction "12_12") (pintype "passive"))
      (node (ref "JP8") (pin "12") (pinfunction "12_12") (pintype "passive"))
    )
    (net (code "75") (name "Net-(LED1-PadA)") (class "Default")
      (node (ref "LED1") (pin "A") (pinfunction "A_A") (pintype "passive"))
      (node (ref "R1") (pin "1") (pinfunction "1_1") (pintype "passive"))
    )
    (net (code "76") (name "Net-(LED2-PadA)") (class "Default")
      (node (ref "LED2") (pin "A") (pinfunction "A_A") (pintype "passive"))
      (node (ref "R2") (pin "1") (pinfunction "1_1") (pintype "passive"))
    )
    (net (code "77") (name "Net-(LED3-PadA)") (class "Default")
      (node (ref "LED3") (pin "A") (pinfunction "A_A") (pintype "passive"))
      (node (ref "R3") (pin "1") (pinfunction "1_1") (pintype "passive"))
    )
    (net (code "78") (name "Net-(LED4-PadA)") (class "Default")
      (node (ref "LED4") (pin "A") (pinfunction "A_A") (pintype "passive"))
      (node (ref "R4") (pin "1") (pinfunction "1_1") (pintype "passive"))
    )
    (net (code "79") (name "Net-(LED5-PadA)") (class "Default")
      (node (ref "LED5") (pin "A") (pinfunction "A_A") (pintype "passive"))
      (node (ref "R5") (pin "1") (pinfunction "1_1") (pintype "passive"))
    )
    (net (code "80") (name "Net-(LED6-PadA)") (class "Default")
      (node (ref "LED6") (pin "A") (pinfunction "A_A") (pintype "passive"))
      (node (ref "R6") (pin "1") (pinfunction "1_1") (pintype "passive"))
    )
    (net (code "81") (name "SCL") (class "Default")
      (node (ref "JP11") (pin "8") (pinfunction "8_8") (pintype "passive"))
      (node (ref "JP14") (pin "8") (pinfunction "8_8") (pintype "passive"))
      (node (ref "JP17") (pin "17") (pinfunction "17_17") (pintype "passive"))
      (node (ref "JP20") (pin "8") (pinfunction "8_8") (pintype "passive"))
      (node (ref "JP7") (pin "17") (pinfunction "17_17") (pintype "passive"))
      (node (ref "JP8") (pin "17") (pinfunction "17_17") (pintype "passive"))
      (node (ref "U$3") (pin "CLK") (pinfunction "SCL_CLK") (pintype "bidirectional"))
      (node (ref "U$5") (pin "CLK") (pinfunction "SCL_CLK") (pintype "bidirectional"))
    )
    (net (code "82") (name "SDA") (class "Default")
      (node (ref "JP11") (pin "9") (pinfunction "9_9") (pintype "passive"))
      (node (ref "JP14") (pin "9") (pinfunction "9_9") (pintype "passive"))
      (node (ref "JP17") (pin "14") (pinfunction "14_14") (pintype "passive"))
      (node (ref "JP20") (pin "9") (pinfunction "9_9") (pintype "passive"))
      (node (ref "JP7") (pin "14") (pinfunction "14_14") (pintype "passive"))
      (node (ref "JP8") (pin "14") (pinfunction "14_14") (pintype "passive"))
      (node (ref "U$3") (pin "DAT") (pinfunction "SDA_DAT") (pintype "bidirectional"))
      (node (ref "U$5") (pin "DAT") (pinfunction "SDA_DAT") (pintype "bidirectional"))
    )
    (net (code "83") (name "V3.3") (class "Default")
      (node (ref "C2") (pin "1") (pinfunction "1_1") (pintype "passive"))
      (node (ref "C4") (pin "1") (pinfunction "1_1") (pintype "passive"))
      (node (ref "IC1") (pin "2") (pinfunction "VOUT_2") (pintype "output"))
      (node (ref "IC2") (pin "2") (pinfunction "VOUT_2") (pintype "output"))
      (node (ref "JP10") (pin "1") (pinfunction "1_1") (pintype "passive"))
      (node (ref "JP10") (pin "10") (pinfunction "10_10") (pintype "passive"))
      (node (ref "JP10") (pin "11") (pinfunction "11_11") (pintype "passive"))
      (node (ref "JP10") (pin "12") (pinfunction "12_12") (pintype "passive"))
      (node (ref "JP10") (pin "13") (pinfunction "13_13") (pintype "passive"))
      (node (ref "JP10") (pin "14") (pinfunction "14_14") (pintype "passive"))
      (node (ref "JP10") (pin "15") (pinfunction "15_15") (pintype "passive"))
      (node (ref "JP10") (pin "16") (pinfunction "16_16") (pintype "passive"))
      (node (ref "JP10") (pin "17") (pinfunction "17_17") (pintype "passive"))
      (node (ref "JP10") (pin "18") (pinfunction "18_18") (pintype "passive"))
      (node (ref "JP10") (pin "19") (pinfunction "19_19") (pintype "passive"))
      (node (ref "JP10") (pin "2") (pinfunction "2_2") (pintype "passive"))
      (node (ref "JP10") (pin "20") (pinfunction "20_20") (pintype "passive"))
      (node (ref "JP10") (pin "21") (pinfunction "21_21") (pintype "passive"))
      (node (ref "JP10") (pin "22") (pinfunction "22_22") (pintype "passive"))
      (node (ref "JP10") (pin "23") (pinfunction "23_23") (pintype "passive"))
      (node (ref "JP10") (pin "24") (pinfunction "24_24") (pintype "passive"))
      (node (ref "JP10") (pin "3") (pinfunction "3_3") (pintype "passive"))
      (node (ref "JP10") (pin "4") (pinfunction "4_4") (pintype "passive"))
      (node (ref "JP10") (pin "5") (pinfunction "5_5") (pintype "passive"))
      (node (ref "JP10") (pin "6") (pinfunction "6_6") (pintype "passive"))
      (node (ref "JP10") (pin "7") (pinfunction "7_7") (pintype "passive"))
      (node (ref "JP10") (pin "8") (pinfunction "8_8") (pintype "passive"))
      (node (ref "JP10") (pin "9") (pinfunction "9_9") (pintype "passive"))
      (node (ref "JP12") (pin "15") (pinfunction "15_15") (pintype "passive"))
      (node (ref "JP2") (pin "19") (pinfunction "19_19") (pintype "passive"))
      (node (ref "JP21") (pin "15") (pinfunction "15_15") (pintype "passive"))
      (node (ref "JP3") (pin "19") (pinfunction "19_19") (pintype "passive"))
      (node (ref "JP4") (pin "1") (pinfunction "1_1") (pintype "passive"))
      (node (ref "JP4") (pin "10") (pinfunction "10_10") (pintype "passive"))
      (node (ref "JP4") (pin "11") (pinfunction "11_11") (pintype "passive"))
      (node (ref "JP4") (pin "12") (pinfunction "12_12") (pintype "passive"))
      (node (ref "JP4") (pin "13") (pinfunction "13_13") (pintype "passive"))
      (node (ref "JP4") (pin "14") (pinfunction "14_14") (pintype "passive"))
      (node (ref "JP4") (pin "15") (pinfunction "15_15") (pintype "passive"))
      (node (ref "JP4") (pin "16") (pinfunction "16_16") (pintype "passive"))
      (node (ref "JP4") (pin "17") (pinfunction "17_17") (pintype "passive"))
      (node (ref "JP4") (pin "18") (pinfunction "18_18") (pintype "passive"))
      (node (ref "JP4") (pin "19") (pinfunction "19_19") (pintype "passive"))
      (node (ref "JP4") (pin "2") (pinfunction "2_2") (pintype "passive"))
      (node (ref "JP4") (pin "3") (pinfunction "3_3") (pintype "passive"))
      (node (ref "JP4") (pin "4") (pinfunction "4_4") (pintype "passive"))
      (node (ref "JP4") (pin "5") (pinfunction "5_5") (pintype "passive"))
      (node (ref "JP4") (pin "6") (pinfunction "6_6") (pintype "passive"))
      (node (ref "JP4") (pin "7") (pinfunction "7_7") (pintype "passive"))
      (node (ref "JP4") (pin "8") (pinfunction "8_8") (pintype "passive"))
      (node (ref "JP4") (pin "9") (pinfunction "9_9") (pintype "passive"))
      (node (ref "JP6") (pin "19") (pinfunction "19_19") (pintype "passive"))
      (node (ref "JP9") (pin "15") (pinfunction "15_15") (pintype "passive"))
      (node (ref "R3") (pin "2") (pinfunction "2_2") (pintype "passive"))
      (node (ref "R6") (pin "2") (pinfunction "2_2") (pintype "passive"))
      (node (ref "U$3") (pin "PWR") (pinfunction "VCC_PWR") (pintype "bidirectional"))
      (node (ref "U$5") (pin "PWR") (pinfunction "VCC_PWR") (pintype "bidirectional"))
    )
    (net (code "84") (name "VCC") (class "Default")
      (node (ref "C1") (pin "1") (pinfunction "1_1") (pintype "passive"))
      (node (ref "C3") (pin "1") (pinfunction "1_1") (pintype "passive"))
      (node (ref "F3") (pin "P$1") (pinfunction "P$1_P$1") (pintype "bidirectional"))
      (node (ref "F4") (pin "P$1") (pinfunction "P$1_P$1") (pintype "bidirectional"))
      (node (ref "IC1") (pin "3") (pinfunction "VIN_3") (pintype "input"))
      (node (ref "IC2") (pin "3") (pinfunction "VIN_3") (pintype "input"))
      (node (ref "JP15") (pin "1") (pinfunction "1_1") (pintype "passive"))
      (node (ref "JP15") (pin "10") (pinfunction "10_10") (pintype "passive"))
      (node (ref "JP15") (pin "11") (pinfunction "11_11") (pintype "passive"))
      (node (ref "JP15") (pin "12") (pinfunction "12_12") (pintype "passive"))
      (node (ref "JP15") (pin "13") (pinfunction "13_13") (pintype "passive"))
      (node (ref "JP15") (pin "14") (pinfunction "14_14") (pintype "passive"))
      (node (ref "JP15") (pin "15") (pinfunction "15_15") (pintype "passive"))
      (node (ref "JP15") (pin "16") (pinfunction "16_16") (pintype "passive"))
      (node (ref "JP15") (pin "17") (pinfunction "17_17") (pintype "passive"))
      (node (ref "JP15") (pin "18") (pinfunction "18_18") (pintype "passive"))
      (node (ref "JP15") (pin "19") (pinfunction "19_19") (pintype "passive"))
      (node (ref "JP15") (pin "2") (pinfunction "2_2") (pintype "passive"))
      (node (ref "JP15") (pin "20") (pinfunction "20_20") (pintype "passive"))
      (node (ref "JP15") (pin "21") (pinfunction "21_21") (pintype "passive"))
      (node (ref "JP15") (pin "22") (pinfunction "22_22") (pintype "passive"))
      (node (ref "JP15") (pin "23") (pinfunction "23_23") (pintype "passive"))
      (node (ref "JP15") (pin "24") (pinfunction "24_24") (pintype "passive"))
      (node (ref "JP15") (pin "3") (pinfunction "3_3") (pintype "passive"))
      (node (ref "JP15") (pin "4") (pinfunction "4_4") (pintype "passive"))
      (node (ref "JP15") (pin "5") (pinfunction "5_5") (pintype "passive"))
      (node (ref "JP15") (pin "6") (pinfunction "6_6") (pintype "passive"))
      (node (ref "JP15") (pin "7") (pinfunction "7_7") (pintype "passive"))
      (node (ref "JP15") (pin "8") (pinfunction "8_8") (pintype "passive"))
      (node (ref "JP15") (pin "9") (pinfunction "9_9") (pintype "passive"))
      (node (ref "JP18") (pin "1") (pinfunction "1_1") (pintype "passive"))
      (node (ref "JP18") (pin "10") (pinfunction "10_10") (pintype "passive"))
      (node (ref "JP18") (pin "11") (pinfunction "11_11") (pintype "passive"))
      (node (ref "JP18") (pin "12") (pinfunction "12_12") (pintype "passive"))
      (node (ref "JP18") (pin "13") (pinfunction "13_13") (pintype "passive"))
      (node (ref "JP18") (pin "14") (pinfunction "14_14") (pintype "passive"))
      (node (ref "JP18") (pin "15") (pinfunction "15_15") (pintype "passive"))
      (node (ref "JP18") (pin "16") (pinfunction "16_16") (pintype "passive"))
      (node (ref "JP18") (pin "17") (pinfunction "17_17") (pintype "passive"))
      (node (ref "JP18") (pin "18") (pinfunction "18_18") (pintype "passive"))
      (node (ref "JP18") (pin "19") (pinfunction "19_19") (pintype "passive"))
      (node (ref "JP18") (pin "2") (pinfunction "2_2") (pintype "passive"))
      (node (ref "JP18") (pin "3") (pinfunction "3_3") (pintype "passive"))
      (node (ref "JP18") (pin "4") (pinfunction "4_4") (pintype "passive"))
      (node (ref "JP18") (pin "5") (pinfunction "5_5") (pintype "passive"))
      (node (ref "JP18") (pin "6") (pinfunction "6_6") (pintype "passive"))
      (node (ref "JP18") (pin "7") (pinfunction "7_7") (pintype "passive"))
      (node (ref "JP18") (pin "8") (pinfunction "8_8") (pintype "passive"))
      (node (ref "JP18") (pin "9") (pinfunction "9_9") (pintype "passive"))
      (node (ref "R1") (pin "2") (pinfunction "2_2") (pintype "passive"))
      (node (ref "R4") (pin "2") (pinfunction "2_2") (pintype "passive"))
    )
  )
)
